# Heart.net
KiCad netlist of a schematic drawn in Altium Designer
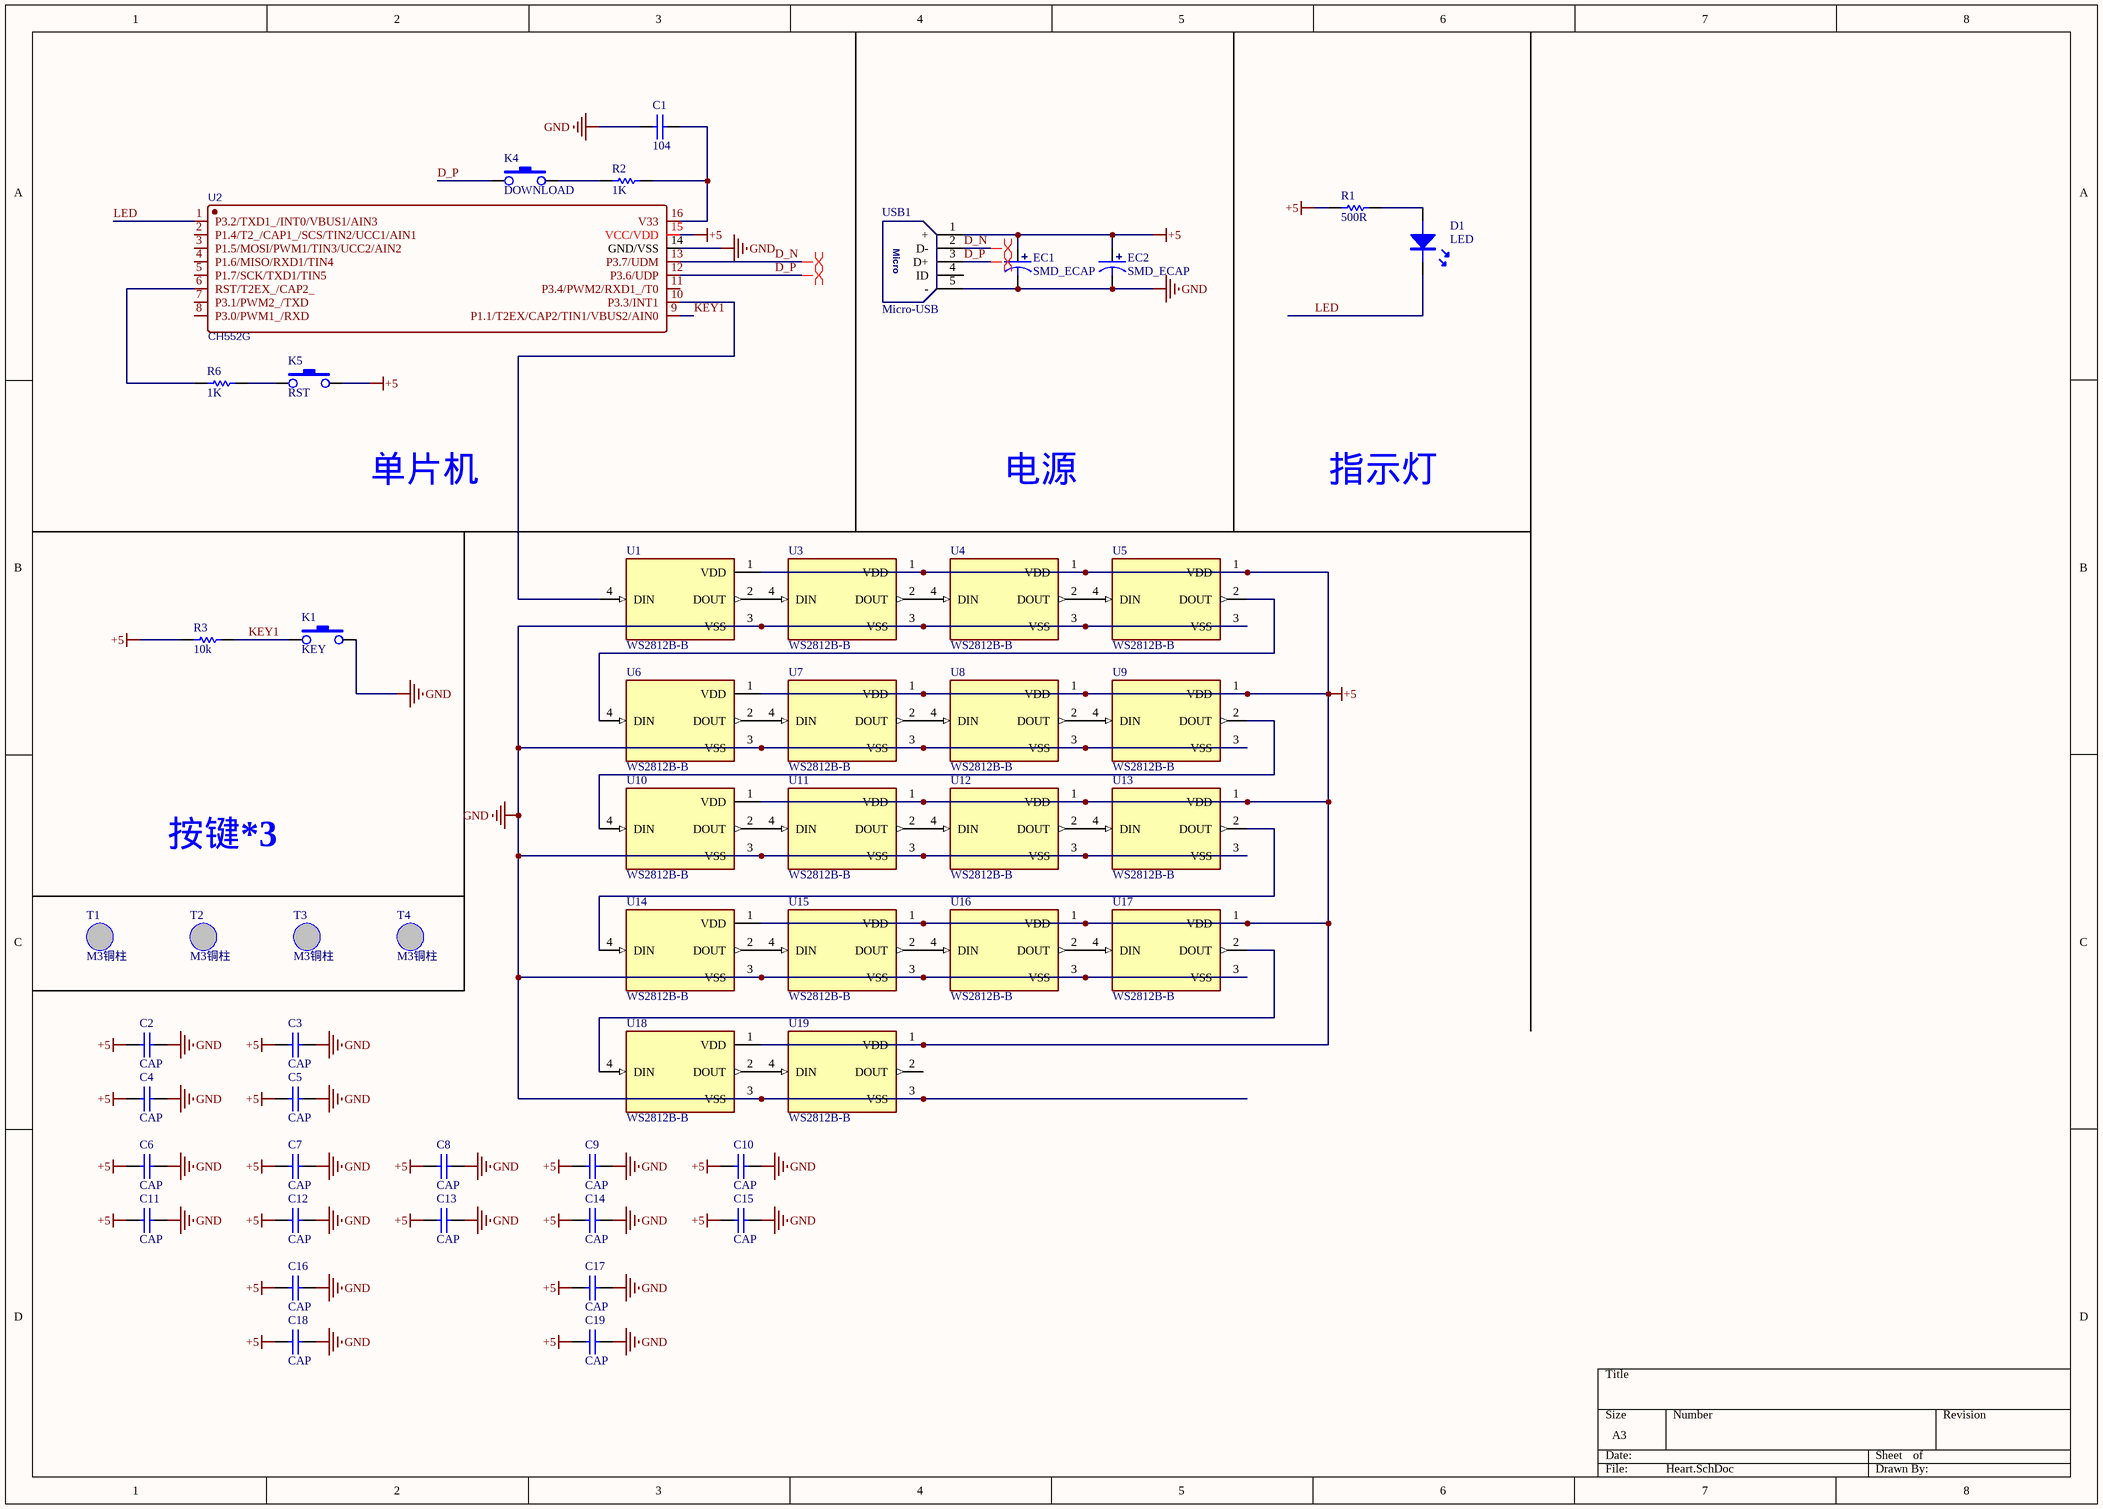
[diagram p0: Heart.SchDoc]

(export (version "E")
  (design (tool "Eeschema 10.0.6"))
  (components
    (comp (ref "C1")
      (value "104")
      (footprint "0805C")
      (description "无极性电容")
      (libsource (lib "常用元件-电容") (part "CAP"))
    )
    (comp (ref "C2")
      (value "CAP")
      (footprint "0805C")
      (description "无极性电容")
      (libsource (lib "常用元件-电容") (part "CAP"))
    )
    (comp (ref "C3")
      (value "CAP")
      (footprint "0805C")
      (description "无极性电容")
      (libsource (lib "常用元件-电容") (part "CAP"))
    )
    (comp (ref "C4")
      (value "CAP")
      (footprint "0805C")
      (description "无极性电容")
      (libsource (lib "常用元件-电容") (part "CAP"))
    )
    (comp (ref "C5")
      (value "CAP")
      (footprint "0805C")
      (description "无极性电容")
      (libsource (lib "常用元件-电容") (part "CAP"))
    )
    (comp (ref "C6")
      (value "CAP")
      (footprint "0805C")
      (description "无极性电容")
      (libsource (lib "常用元件-电容") (part "CAP"))
    )
    (comp (ref "C7")
      (value "CAP")
      (footprint "0805C")
      (description "无极性电容")
      (libsource (lib "常用元件-电容") (part "CAP"))
    )
    (comp (ref "C8")
      (value "CAP")
      (footprint "0805C")
      (description "无极性电容")
      (libsource (lib "常用元件-电容") (part "CAP"))
    )
    (comp (ref "C9")
      (value "CAP")
      (footprint "0805C")
      (description "无极性电容")
      (libsource (lib "常用元件-电容") (part "CAP"))
    )
    (comp (ref "C10")
      (value "CAP")
      (footprint "0805C")
      (description "无极性电容")
      (libsource (lib "常用元件-电容") (part "CAP"))
    )
    (comp (ref "C11")
      (value "CAP")
      (footprint "0805C")
      (description "无极性电容")
      (libsource (lib "常用元件-电容") (part "CAP"))
    )
    (comp (ref "C12")
      (value "CAP")
      (footprint "0805C")
      (description "无极性电容")
      (libsource (lib "常用元件-电容") (part "CAP"))
    )
    (comp (ref "C13")
      (value "CAP")
      (footprint "0805C")
      (description "无极性电容")
      (libsource (lib "常用元件-电容") (part "CAP"))
    )
    (comp (ref "C14")
      (value "CAP")
      (footprint "0805C")
      (description "无极性电容")
      (libsource (lib "常用元件-电容") (part "CAP"))
    )
    (comp (ref "C15")
      (value "CAP")
      (footprint "0805C")
      (description "无极性电容")
      (libsource (lib "常用元件-电容") (part "CAP"))
    )
    (comp (ref "C16")
      (value "CAP")
      (footprint "0805C")
      (description "无极性电容")
      (libsource (lib "常用元件-电容") (part "CAP"))
    )
    (comp (ref "C17")
      (value "CAP")
      (footprint "0805C")
      (description "无极性电容")
      (libsource (lib "常用元件-电容") (part "CAP"))
    )
    (comp (ref "C18")
      (value "CAP")
      (footprint "0805C")
      (description "无极性电容")
      (libsource (lib "常用元件-电容") (part "CAP"))
    )
    (comp (ref "C19")
      (value "CAP")
      (footprint "0805C")
      (description "无极性电容")
      (libsource (lib "常用元件-电容") (part "CAP"))
    )
    (comp (ref "D1") (value "LED") (footprint "LED-0805G") (libsource (lib "常用元件-LED") (part "LED")))
    (comp (ref "EC1")
      (value "SMD_ECAP")
      (footprint "SMD-EC5.0X5.3X5.4")
      (description "贴片电解电容")
      (libsource (lib "常用元件-电容") (part "SMD_ECAP"))
    )
    (comp (ref "EC2")
      (value "SMD_ECAP")
      (footprint "SMD-EC5.0X5.3X5.4")
      (description "贴片电解电容")
      (libsource (lib "常用元件-电容") (part "SMD_ECAP"))
    )
    (comp (ref "K1") (value "KEY") (footprint "SMD-3X6X5") (libsource (lib "开关-轻触开关") (part "KEY")))
    (comp (ref "K4") (value "DOWNLOAD") (footprint "SMD-3X6X5") (libsource (lib "开关-轻触开关") (part "KEY")))
    (comp (ref "K5") (value "RST") (footprint "SMD-3X6X5") (libsource (lib "开关-轻触开关") (part "KEY")))
    (comp (ref "R1") (value "500R") (footprint "0805R") (libsource (lib "常用元件-电阻") (part "RES")))
    (comp (ref "R2") (value "1K") (footprint "0805R") (libsource (lib "常用元件-电阻") (part "RES")))
    (comp (ref "R3") (value "10k") (footprint "0805R") (libsource (lib "常用元件-电阻") (part "RES")))
    (comp (ref "R6") (value "1K") (footprint "0805R") (libsource (lib "常用元件-电阻") (part "RES")))
    (comp (ref "T1") (value "M3铜柱") (footprint "M3 单孔") (libsource (lib "M3铜柱") (part "M3铜柱")))
    (comp (ref "T2") (value "M3铜柱") (footprint "M3 单孔") (libsource (lib "M3铜柱") (part "M3铜柱")))
    (comp (ref "T3") (value "M3铜柱") (footprint "M3 单孔") (libsource (lib "M3铜柱") (part "M3铜柱")))
    (comp (ref "T4") (value "M3铜柱") (footprint "M3 单孔") (libsource (lib "M3铜柱") (part "M3铜柱")))
    (comp (ref "U1")
      (value "WS2812B-B")
      (footprint "LED_WS2812B-B++")
      (description "Intelligent control LED integrated light source")
      (fields (field (name "MF") "{'manufacturer': u'Worldsemi'}"))
      (libsource (lib "SnapEDA_Library") (part "WS2812B-B"))
    )
    (comp (ref "U2")
      (value "CH552G")
      (footprint "SOP16")
      (fields (field (name "BOM_SUPPLIER PART") "C111292"))
      (libsource (lib "CH552G") (part "CH552G"))
    )
    (comp (ref "U3")
      (value "WS2812B-B")
      (footprint "LED_WS2812B-B++")
      (description "Intelligent control LED integrated light source")
      (fields (field (name "MF") "{'manufacturer': u'Worldsemi'}"))
      (libsource (lib "SnapEDA_Library") (part "WS2812B-B"))
    )
    (comp (ref "U4")
      (value "WS2812B-B")
      (footprint "LED_WS2812B-B++")
      (description "Intelligent control LED integrated light source")
      (fields (field (name "MF") "{'manufacturer': u'Worldsemi'}"))
      (libsource (lib "SnapEDA_Library") (part "WS2812B-B"))
    )
    (comp (ref "U5")
      (value "WS2812B-B")
      (footprint "LED_WS2812B-B++")
      (description "Intelligent control LED integrated light source")
      (fields (field (name "MF") "{'manufacturer': u'Worldsemi'}"))
      (libsource (lib "SnapEDA_Library") (part "WS2812B-B"))
    )
    (comp (ref "U6")
      (value "WS2812B-B")
      (footprint "LED_WS2812B-B++")
      (description "Intelligent control LED integrated light source")
      (fields (field (name "MF") "{'manufacturer': u'Worldsemi'}"))
      (libsource (lib "SnapEDA_Library") (part "WS2812B-B"))
    )
    (comp (ref "U7")
      (value "WS2812B-B")
      (footprint "LED_WS2812B-B++")
      (description "Intelligent control LED integrated light source")
      (fields (field (name "MF") "{'manufacturer': u'Worldsemi'}"))
      (libsource (lib "SnapEDA_Library") (part "WS2812B-B"))
    )
    (comp (ref "U8")
      (value "WS2812B-B")
      (footprint "LED_WS2812B-B++")
      (description "Intelligent control LED integrated light source")
      (fields (field (name "MF") "{'manufacturer': u'Worldsemi'}"))
      (libsource (lib "SnapEDA_Library") (part "WS2812B-B"))
    )
    (comp (ref "U9")
      (value "WS2812B-B")
      (footprint "LED_WS2812B-B++")
      (description "Intelligent control LED integrated light source")
      (fields (field (name "MF") "{'manufacturer': u'Worldsemi'}"))
      (libsource (lib "SnapEDA_Library") (part "WS2812B-B"))
    )
    (comp (ref "U10")
      (value "WS2812B-B")
      (footprint "LED_WS2812B-B++")
      (description "Intelligent control LED integrated light source")
      (fields (field (name "MF") "{'manufacturer': u'Worldsemi'}"))
      (libsource (lib "SnapEDA_Library") (part "WS2812B-B"))
    )
    (comp (ref "U11")
      (value "WS2812B-B")
      (footprint "LED_WS2812B-B++")
      (description "Intelligent control LED integrated light source")
      (fields (field (name "MF") "{'manufacturer': u'Worldsemi'}"))
      (libsource (lib "SnapEDA_Library") (part "WS2812B-B"))
    )
    (comp (ref "U12")
      (value "WS2812B-B")
      (footprint "LED_WS2812B-B++")
      (description "Intelligent control LED integrated light source")
      (fields (field (name "MF") "{'manufacturer': u'Worldsemi'}"))
      (libsource (lib "SnapEDA_Library") (part "WS2812B-B"))
    )
    (comp (ref "U13")
      (value "WS2812B-B")
      (footprint "LED_WS2812B-B++")
      (description "Intelligent control LED integrated light source")
      (fields (field (name "MF") "{'manufacturer': u'Worldsemi'}"))
      (libsource (lib "SnapEDA_Library") (part "WS2812B-B"))
    )
    (comp (ref "U14")
      (value "WS2812B-B")
      (footprint "LED_WS2812B-B++")
      (description "Intelligent control LED integrated light source")
      (fields (field (name "MF") "{'manufacturer': u'Worldsemi'}"))
      (libsource (lib "SnapEDA_Library") (part "WS2812B-B"))
    )
    (comp (ref "U15")
      (value "WS2812B-B")
      (footprint "LED_WS2812B-B++")
      (description "Intelligent control LED integrated light source")
      (fields (field (name "MF") "{'manufacturer': u'Worldsemi'}"))
      (libsource (lib "SnapEDA_Library") (part "WS2812B-B"))
    )
    (comp (ref "U16")
      (value "WS2812B-B")
      (footprint "LED_WS2812B-B++")
      (description "Intelligent control LED integrated light source")
      (fields (field (name "MF") "{'manufacturer': u'Worldsemi'}"))
      (libsource (lib "SnapEDA_Library") (part "WS2812B-B"))
    )
    (comp (ref "U17")
      (value "WS2812B-B")
      (footprint "LED_WS2812B-B++")
      (description "Intelligent control LED integrated light source")
      (fields (field (name "MF") "{'manufacturer': u'Worldsemi'}"))
      (libsource (lib "SnapEDA_Library") (part "WS2812B-B"))
    )
    (comp (ref "U18")
      (value "WS2812B-B")
      (footprint "LED_WS2812B-B++")
      (description "Intelligent control LED integrated light source")
      (fields (field (name "MF") "{'manufacturer': u'Worldsemi'}"))
      (libsource (lib "SnapEDA_Library") (part "WS2812B-B"))
    )
    (comp (ref "U19")
      (value "WS2812B-B")
      (footprint "LED_WS2812B-B++")
      (description "Intelligent control LED integrated light source")
      (fields (field (name "MF") "{'manufacturer': u'Worldsemi'}"))
      (libsource (lib "SnapEDA_Library") (part "WS2812B-B"))
    )
    (comp (ref "USB1")
      (value "Micro-USB")
      (footprint "USB-MICRO_A++")
      (libsource (lib "插座-USB连接器") (part "Micro-USB"))
    )
  )
  (nets
    (net (code "1") (name "+5") (class "Default")
      (node (ref "C10") (pin "1") (pinfunction "1_1") (pintype "passive"))
      (node (ref "C11") (pin "1") (pinfunction "1_1") (pintype "passive"))
      (node (ref "C12") (pin "1") (pinfunction "1_1") (pintype "passive"))
      (node (ref "C13") (pin "1") (pinfunction "1_1") (pintype "passive"))
      (node (ref "C14") (pin "1") (pinfunction "1_1") (pintype "passive"))
      (node (ref "C15") (pin "1") (pinfunction "1_1") (pintype "passive"))
      (node (ref "C16") (pin "1") (pinfunction "1_1") (pintype "passive"))
      (node (ref "C17") (pin "1") (pinfunction "1_1") (pintype "passive"))
      (node (ref "C18") (pin "1") (pinfunction "1_1") (pintype "passive"))
      (node (ref "C19") (pin "1") (pinfunction "1_1") (pintype "passive"))
      (node (ref "C2") (pin "1") (pinfunction "1_1") (pintype "passive"))
      (node (ref "C3") (pin "1") (pinfunction "1_1") (pintype "passive"))
      (node (ref "C4") (pin "1") (pinfunction "1_1") (pintype "passive"))
      (node (ref "C5") (pin "1") (pinfunction "1_1") (pintype "passive"))
      (node (ref "C6") (pin "1") (pinfunction "1_1") (pintype "passive"))
      (node (ref "C7") (pin "1") (pinfunction "1_1") (pintype "passive"))
      (node (ref "C8") (pin "1") (pinfunction "1_1") (pintype "passive"))
      (node (ref "C9") (pin "1") (pinfunction "1_1") (pintype "passive"))
      (node (ref "EC1") (pin "1") (pinfunction "1_1") (pintype "passive"))
      (node (ref "EC2") (pin "1") (pinfunction "1_1") (pintype "passive"))
      (node (ref "K5") (pin "3") (pinfunction "3_3") (pintype "passive"))
      (node (ref "R1") (pin "1") (pinfunction "1_1") (pintype "passive"))
      (node (ref "R3") (pin "1") (pinfunction "1_1") (pintype "passive"))
      (node (ref "U1") (pin "1") (pinfunction "VDD_1") (pintype "power_in"))
      (node (ref "U10") (pin "1") (pinfunction "VDD_1") (pintype "power_in"))
      (node (ref "U11") (pin "1") (pinfunction "VDD_1") (pintype "power_in"))
      (node (ref "U12") (pin "1") (pinfunction "VDD_1") (pintype "power_in"))
      (node (ref "U13") (pin "1") (pinfunction "VDD_1") (pintype "power_in"))
      (node (ref "U14") (pin "1") (pinfunction "VDD_1") (pintype "power_in"))
      (node (ref "U15") (pin "1") (pinfunction "VDD_1") (pintype "power_in"))
      (node (ref "U16") (pin "1") (pinfunction "VDD_1") (pintype "power_in"))
      (node (ref "U17") (pin "1") (pinfunction "VDD_1") (pintype "power_in"))
      (node (ref "U18") (pin "1") (pinfunction "VDD_1") (pintype "power_in"))
      (node (ref "U19") (pin "1") (pinfunction "VDD_1") (pintype "power_in"))
      (node (ref "U2") (pin "15") (pinfunction "VCC/VDD_15") (pintype "passive"))
      (node (ref "U3") (pin "1") (pinfunction "VDD_1") (pintype "power_in"))
      (node (ref "U4") (pin "1") (pinfunction "VDD_1") (pintype "power_in"))
      (node (ref "U5") (pin "1") (pinfunction "VDD_1") (pintype "power_in"))
      (node (ref "U6") (pin "1") (pinfunction "VDD_1") (pintype "power_in"))
      (node (ref "U7") (pin "1") (pinfunction "VDD_1") (pintype "power_in"))
      (node (ref "U8") (pin "1") (pinfunction "VDD_1") (pintype "power_in"))
      (node (ref "U9") (pin "1") (pinfunction "VDD_1") (pintype "power_in"))
      (node (ref "USB1") (pin "1") (pinfunction "+_1") (pintype "passive"))
    )
    (net (code "2") (name "/D_N") (class "Default")
      (node (ref "U2") (pin "13") (pinfunction "P3.7/UDM_13") (pintype "passive"))
      (node (ref "USB1") (pin "2") (pinfunction "D-_2") (pintype "passive"))
    )
    (net (code "3") (name "/D_P") (class "Default")
      (node (ref "K4") (pin "1") (pinfunction "1_1") (pintype "passive"))
      (node (ref "U2") (pin "12") (pinfunction "P3.6/UDP_12") (pintype "passive"))
      (node (ref "USB1") (pin "3") (pinfunction "D+_3") (pintype "passive"))
    )
    (net (code "4") (name "/KEY1") (class "Default")
      (node (ref "K1") (pin "1") (pinfunction "1_1") (pintype "passive"))
      (node (ref "R3") (pin "2") (pinfunction "2_2") (pintype "passive"))
      (node (ref "U2") (pin "9") (pinfunction "P1.1/T2EX/CAP2/TIN1/VBUS2/AIN0_9") (pintype "passive"))
    )
    (net (code "5") (name "/LED") (class "Default")
      (node (ref "D1") (pin "K") (pinfunction "K_K") (pintype "passive"))
      (node (ref "U2") (pin "1") (pinfunction "P3.2/TXD1_/INT0/VBUS1/AIN3_1") (pintype "passive"))
    )
    (net (code "6") (name "GND") (class "Default")
      (node (ref "C1") (pin "2") (pinfunction "2_2") (pintype "passive"))
      (node (ref "C10") (pin "2") (pinfunction "2_2") (pintype "passive"))
      (node (ref "C11") (pin "2") (pinfunction "2_2") (pintype "passive"))
      (node (ref "C12") (pin "2") (pinfunction "2_2") (pintype "passive"))
      (node (ref "C13") (pin "2") (pinfunction "2_2") (pintype "passive"))
      (node (ref "C14") (pin "2") (pinfunction "2_2") (pintype "passive"))
      (node (ref "C15") (pin "2") (pinfunction "2_2") (pintype "passive"))
      (node (ref "C16") (pin "2") (pinfunction "2_2") (pintype "passive"))
      (node (ref "C17") (pin "2") (pinfunction "2_2") (pintype "passive"))
      (node (ref "C18") (pin "2") (pinfunction "2_2") (pintype "passive"))
      (node (ref "C19") (pin "2") (pinfunction "2_2") (pintype "passive"))
      (node (ref "C2") (pin "2") (pinfunction "2_2") (pintype "passive"))
      (node (ref "C3") (pin "2") (pinfunction "2_2") (pintype "passive"))
      (node (ref "C4") (pin "2") (pinfunction "2_2") (pintype "passive"))
      (node (ref "C5") (pin "2") (pinfunction "2_2") (pintype "passive"))
      (node (ref "C6") (pin "2") (pinfunction "2_2") (pintype "passive"))
      (node (ref "C7") (pin "2") (pinfunction "2_2") (pintype "passive"))
      (node (ref "C8") (pin "2") (pinfunction "2_2") (pintype "passive"))
      (node (ref "C9") (pin "2") (pinfunction "2_2") (pintype "passive"))
      (node (ref "EC1") (pin "2") (pinfunction "2_2") (pintype "passive"))
      (node (ref "EC2") (pin "2") (pinfunction "2_2") (pintype "passive"))
      (node (ref "K1") (pin "3") (pinfunction "3_3") (pintype "passive"))
      (node (ref "U1") (pin "3") (pinfunction "VSS_3") (pintype "power_in"))
      (node (ref "U10") (pin "3") (pinfunction "VSS_3") (pintype "power_in"))
      (node (ref "U11") (pin "3") (pinfunction "VSS_3") (pintype "power_in"))
      (node (ref "U12") (pin "3") (pinfunction "VSS_3") (pintype "power_in"))
      (node (ref "U13") (pin "3") (pinfunction "VSS_3") (pintype "power_in"))
      (node (ref "U14") (pin "3") (pinfunction "VSS_3") (pintype "power_in"))
      (node (ref "U15") (pin "3") (pinfunction "VSS_3") (pintype "power_in"))
      (node (ref "U16") (pin "3") (pinfunction "VSS_3") (pintype "power_in"))
      (node (ref "U17") (pin "3") (pinfunction "VSS_3") (pintype "power_in"))
      (node (ref "U18") (pin "3") (pinfunction "VSS_3") (pintype "power_in"))
      (node (ref "U19") (pin "3") (pinfunction "VSS_3") (pintype "power_in"))
      (node (ref "U2") (pin "14") (pinfunction "GND/VSS_14") (pintype "passive"))
      (node (ref "U3") (pin "3") (pinfunction "VSS_3") (pintype "power_in"))
      (node (ref "U4") (pin "3") (pinfunction "VSS_3") (pintype "power_in"))
      (node (ref "U5") (pin "3") (pinfunction "VSS_3") (pintype "power_in"))
      (node (ref "U6") (pin "3") (pinfunction "VSS_3") (pintype "power_in"))
      (node (ref "U7") (pin "3") (pinfunction "VSS_3") (pintype "power_in"))
      (node (ref "U8") (pin "3") (pinfunction "VSS_3") (pintype "power_in"))
      (node (ref "U9") (pin "3") (pinfunction "VSS_3") (pintype "power_in"))
      (node (ref "USB1") (pin "5") (pinfunction "-_5") (pintype "passive"))
    )
    (net (code "7") (name "Net-(D1-PadA)") (class "Default")
      (node (ref "D1") (pin "A") (pinfunction "A_A") (pintype "passive"))
      (node (ref "R1") (pin "2") (pinfunction "2_2") (pintype "passive"))
    )
    (net (code "8") (name "Net-(K4-Pad3)") (class "Default")
      (node (ref "K4") (pin "3") (pinfunction "3_3") (pintype "passive"))
      (node (ref "R2") (pin "1") (pinfunction "1_1") (pintype "passive"))
    )
    (net (code "9") (name "Net-(K5-Pad1)") (class "Default")
      (node (ref "K5") (pin "1") (pinfunction "1_1") (pintype "passive"))
      (node (ref "R6") (pin "1") (pinfunction "1_1") (pintype "passive"))
    )
    (net (code "10") (name "Net-(U1-DIN)") (class "Default")
      (node (ref "U1") (pin "4") (pinfunction "DIN_4") (pintype "input"))
      (node (ref "U2") (pin "10") (pinfunction "P3.3/INT1_10") (pintype "passive"))
    )
    (net (code "11") (name "Net-(U1-DOUT)") (class "Default")
      (node (ref "U1") (pin "2") (pinfunction "DOUT_2") (pintype "output"))
      (node (ref "U3") (pin "4") (pinfunction "DIN_4") (pintype "input"))
    )
    (net (code "12") (name "Net-(U2-RST{slash}T2EX_{slash}CAP2_)") (class "Default")
      (node (ref "R6") (pin "2") (pinfunction "2_2") (pintype "passive"))
      (node (ref "U2") (pin "6") (pinfunction "RST/T2EX_/CAP2__6") (pintype "passive"))
    )
    (net (code "13") (name "Net-(U2-V33)") (class "Default")
      (node (ref "C1") (pin "1") (pinfunction "1_1") (pintype "passive"))
      (node (ref "R2") (pin "2") (pinfunction "2_2") (pintype "passive"))
      (node (ref "U2") (pin "16") (pinfunction "V33_16") (pintype "passive"))
    )
    (net (code "14") (name "Net-(U3-DOUT)") (class "Default")
      (node (ref "U3") (pin "2") (pinfunction "DOUT_2") (pintype "output"))
      (node (ref "U4") (pin "4") (pinfunction "DIN_4") (pintype "input"))
    )
    (net (code "15") (name "Net-(U4-DOUT)") (class "Default")
      (node (ref "U4") (pin "2") (pinfunction "DOUT_2") (pintype "output"))
      (node (ref "U5") (pin "4") (pinfunction "DIN_4") (pintype "input"))
    )
    (net (code "16") (name "Net-(U5-DOUT)") (class "Default")
      (node (ref "U5") (pin "2") (pinfunction "DOUT_2") (pintype "output"))
      (node (ref "U6") (pin "4") (pinfunction "DIN_4") (pintype "input"))
    )
    (net (code "17") (name "Net-(U6-DOUT)") (class "Default")
      (node (ref "U6") (pin "2") (pinfunction "DOUT_2") (pintype "output"))
      (node (ref "U7") (pin "4") (pinfunction "DIN_4") (pintype "input"))
    )
    (net (code "18") (name "Net-(U7-DOUT)") (class "Default")
      (node (ref "U7") (pin "2") (pinfunction "DOUT_2") (pintype "output"))
      (node (ref "U8") (pin "4") (pinfunction "DIN_4") (pintype "input"))
    )
    (net (code "19") (name "Net-(U8-DOUT)") (class "Default")
      (node (ref "U8") (pin "2") (pinfunction "DOUT_2") (pintype "output"))
      (node (ref "U9") (pin "4") (pinfunction "DIN_4") (pintype "input"))
    )
    (net (code "20") (name "Net-(U10-DIN)") (class "Default")
      (node (ref "U10") (pin "4") (pinfunction "DIN_4") (pintype "input"))
      (node (ref "U9") (pin "2") (pinfunction "DOUT_2") (pintype "output"))
    )
    (net (code "21") (name "Net-(U10-DOUT)") (class "Default")
      (node (ref "U10") (pin "2") (pinfunction "DOUT_2") (pintype "output"))
      (node (ref "U11") (pin "4") (pinfunction "DIN_4") (pintype "input"))
    )
    (net (code "22") (name "Net-(U11-DOUT)") (class "Default")
      (node (ref "U11") (pin "2") (pinfunction "DOUT_2") (pintype "output"))
      (node (ref "U12") (pin "4") (pinfunction "DIN_4") (pintype "input"))
    )
    (net (code "23") (name "Net-(U12-DOUT)") (class "Default")
      (node (ref "U12") (pin "2") (pinfunction "DOUT_2") (pintype "output"))
      (node (ref "U13") (pin "4") (pinfunction "DIN_4") (pintype "input"))
    )
    (net (code "24") (name "Net-(U13-DOUT)") (class "Default")
      (node (ref "U13") (pin "2") (pinfunction "DOUT_2") (pintype "output"))
      (node (ref "U14") (pin "4") (pinfunction "DIN_4") (pintype "input"))
    )
    (net (code "25") (name "Net-(U14-DOUT)") (class "Default")
      (node (ref "U14") (pin "2") (pinfunction "DOUT_2") (pintype "output"))
      (node (ref "U15") (pin "4") (pinfunction "DIN_4") (pintype "input"))
    )
    (net (code "26") (name "Net-(U15-DOUT)") (class "Default")
      (node (ref "U15") (pin "2") (pinfunction "DOUT_2") (pintype "output"))
      (node (ref "U16") (pin "4") (pinfunction "DIN_4") (pintype "input"))
    )
    (net (code "27") (name "Net-(U16-DOUT)") (class "Default")
      (node (ref "U16") (pin "2") (pinfunction "DOUT_2") (pintype "output"))
      (node (ref "U17") (pin "4") (pinfunction "DIN_4") (pintype "input"))
    )
    (net (code "28") (name "Net-(U17-DOUT)") (class "Default")
      (node (ref "U17") (pin "2") (pinfunction "DOUT_2") (pintype "output"))
      (node (ref "U18") (pin "4") (pinfunction "DIN_4") (pintype "input"))
    )
    (net (code "29") (name "Net-(U18-DOUT)") (class "Default")
      (node (ref "U18") (pin "2") (pinfunction "DOUT_2") (pintype "output"))
      (node (ref "U19") (pin "4") (pinfunction "DIN_4") (pintype "input"))
    )
    (net (code "30") (name "unconnected-(U2-P1.4{slash}T2_{slash}CAP1_{slash}SCS{slash}TIN2{slash}UCC1{slash}AIN1-Pad2)") (class "Default")
      (node (ref "U2") (pin "2") (pinfunction "P1.4/T2_/CAP1_/SCS/TIN2/UCC1/AIN1_2") (pintype "passive"))
    )
    (net (code "31") (name "unconnected-(U2-P1.5{slash}MOSI{slash}PWM1{slash}TIN3{slash}UCC2{slash}AIN2-Pad3)") (class "Default")
      (node (ref "U2") (pin "3") (pinfunction "P1.5/MOSI/PWM1/TIN3/UCC2/AIN2_3") (pintype "passive"))
    )
    (net (code "32") (name "unconnected-(U2-P1.6{slash}MISO{slash}RXD1{slash}TIN4-Pad4)") (class "Default")
      (node (ref "U2") (pin "4") (pinfunction "P1.6/MISO/RXD1/TIN4_4") (pintype "passive"))
    )
    (net (code "33") (name "unconnected-(U2-P1.7{slash}SCK{slash}TXD1{slash}TIN5-Pad5)") (class "Default")
      (node (ref "U2") (pin "5") (pinfunction "P1.7/SCK/TXD1/TIN5_5") (pintype "passive"))
    )
    (net (code "34") (name "unconnected-(U2-P3.0{slash}PWM1_{slash}RXD-Pad8)") (class "Default")
      (node (ref "U2") (pin "8") (pinfunction "P3.0/PWM1_/RXD_8") (pintype "passive"))
    )
    (net (code "35") (name "unconnected-(U2-P3.1{slash}PWM2_{slash}TXD-Pad7)") (class "Default")
      (node (ref "U2") (pin "7") (pinfunction "P3.1/PWM2_/TXD_7") (pintype "passive"))
    )
    (net (code "36") (name "unconnected-(U2-P3.4{slash}PWM2{slash}RXD1_{slash}T0-Pad11)") (class "Default")
      (node (ref "U2") (pin "11") (pinfunction "P3.4/PWM2/RXD1_/T0_11") (pintype "passive"))
    )
    (net (code "37") (name "unconnected-(U19-DOUT-Pad2)") (class "Default")
      (node (ref "U19") (pin "2") (pinfunction "DOUT_2") (pintype "output"))
    )
    (net (code "38") (name "unconnected-(USB1-ID-Pad4)") (class "Default")
      (node (ref "USB1") (pin "4") (pinfunction "ID_4") (pintype "passive"))
    )
  )
)
